# sirius1.net
KiCad netlist of a schematic drawn in EAGLE
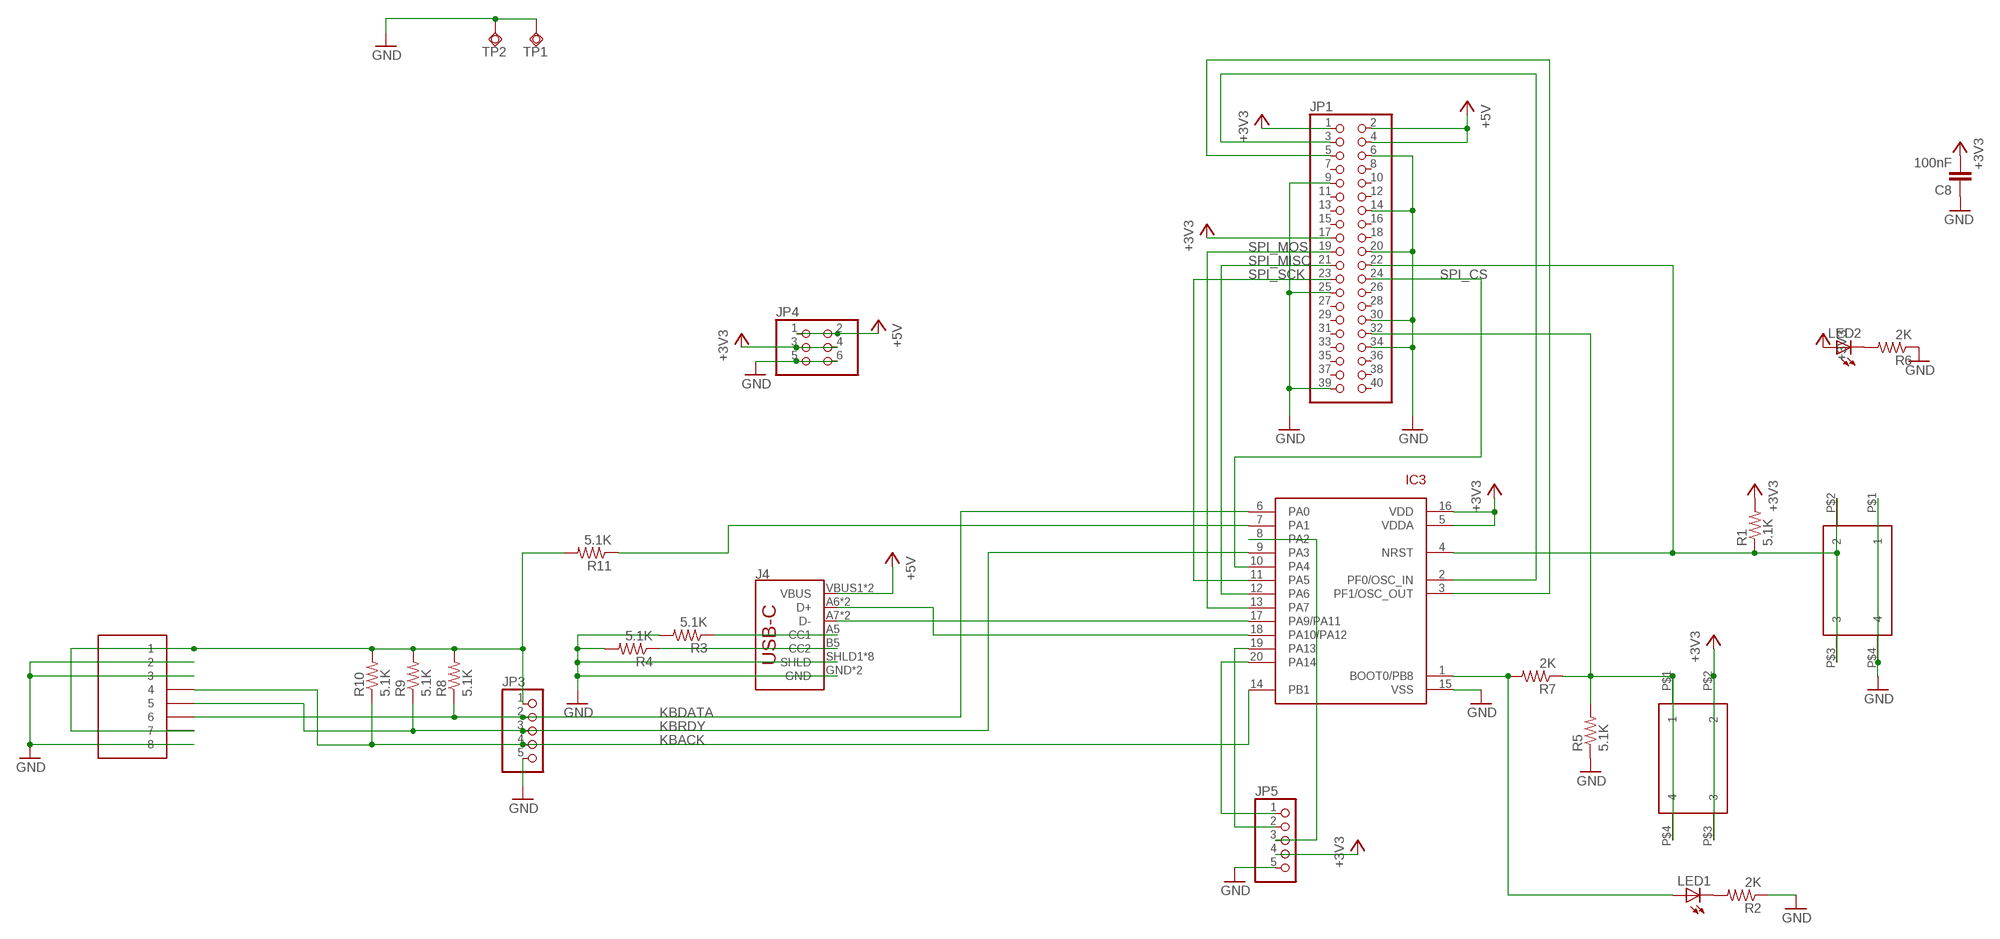
[diagram p0: schematic, sheet 1, part 1 of 2]
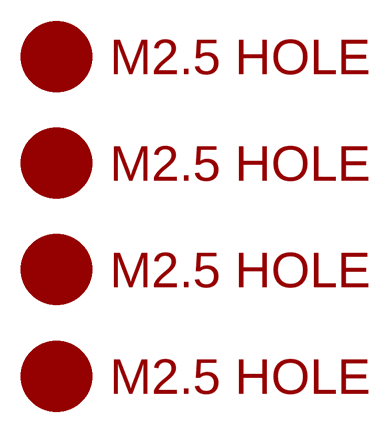
[diagram p1: schematic, sheet 1, part 2 of 2]

(export (version "E")
  (design (tool "Eeschema 10.0.6"))
  (components
    (comp (ref "C8")
      (value "100nF")
      (footprint "eagle-import:0805@1")
      (libsource (lib "eagle-import") (part "CAP0805"))
    )
    (comp (ref "IC3")
      (value "STM32F042F4")
      (footprint "eagle-import:TSSOP20")
      (libsource (lib "eagle-import") (part "STM32F042F4"))
    )
    (comp (ref "J4")
      (value "USB_C16PIN")
      (footprint "eagle-import:USB-C-16P")
      (libsource (lib "eagle-import") (part "USB_C16PIN"))
    )
    (comp (ref "JP1")
      (value "PINHD-2X20-BIG")
      (footprint "eagle-import:2X20-BIG")
      (libsource (lib "eagle-import") (part "PINHD-2X20-BIG"))
    )
    (comp (ref "JP3")
      (value "PINHD-1X5")
      (footprint "eagle-import:1X05")
      (libsource (lib "eagle-import") (part "PINHD-1X5"))
    )
    (comp (ref "JP4")
      (value "PINHD-2X3")
      (footprint "eagle-import:2X03")
      (libsource (lib "eagle-import") (part "PINHD-2X3"))
    )
    (comp (ref "JP5")
      (value "PINHD-1X5")
      (footprint "eagle-import:1X05")
      (libsource (lib "eagle-import") (part "PINHD-1X5"))
    )
    (comp (ref "LED1")
      (value "LEDCHIP-LED0805")
      (footprint "eagle-import:CHIP-LED0805")
      (libsource (lib "eagle-import") (part "LEDCHIP-LED0805"))
    )
    (comp (ref "LED2")
      (value "LEDCHIP-LED0805")
      (footprint "eagle-import:CHIP-LED0805")
      (libsource (lib "eagle-import") (part "LEDCHIP-LED0805"))
    )
    (comp (ref "R1")
      (value "5.1K")
      (footprint "eagle-import:0805")
      (libsource (lib "eagle-import") (part "RESISTOR0805-RES"))
    )
    (comp (ref "R2")
      (value "2K")
      (footprint "eagle-import:0805")
      (libsource (lib "eagle-import") (part "RESISTOR0805-RES"))
    )
    (comp (ref "R3")
      (value "5.1K")
      (footprint "eagle-import:0805")
      (libsource (lib "eagle-import") (part "RESISTOR0805-RES"))
    )
    (comp (ref "R4")
      (value "5.1K")
      (footprint "eagle-import:0805")
      (libsource (lib "eagle-import") (part "RESISTOR0805-RES"))
    )
    (comp (ref "R5")
      (value "5.1K")
      (footprint "eagle-import:0805")
      (libsource (lib "eagle-import") (part "RESISTOR0805-RES"))
    )
    (comp (ref "R6")
      (value "2K")
      (footprint "eagle-import:0805")
      (libsource (lib "eagle-import") (part "RESISTOR0805-RES"))
    )
    (comp (ref "R7")
      (value "2K")
      (footprint "eagle-import:0805")
      (libsource (lib "eagle-import") (part "RESISTOR0805-RES"))
    )
    (comp (ref "R8")
      (value "5.1K")
      (footprint "eagle-import:0805")
      (libsource (lib "eagle-import") (part "RESISTOR0805-RES"))
    )
    (comp (ref "R9")
      (value "5.1K")
      (footprint "eagle-import:0805")
      (libsource (lib "eagle-import") (part "RESISTOR0805-RES"))
    )
    (comp (ref "R10")
      (value "5.1K")
      (footprint "eagle-import:0805")
      (libsource (lib "eagle-import") (part "RESISTOR0805-RES"))
    )
    (comp (ref "R11")
      (value "5.1K")
      (footprint "eagle-import:0805")
      (libsource (lib "eagle-import") (part "RESISTOR0805-RES"))
    )
    (comp (ref "SW1")
      (value "324_SW")
      (footprint "eagle-import:342_SWICH_FOOT")
      (libsource (lib "eagle-import") (part "324_SW"))
    )
    (comp (ref "SW4")
      (value "324_SW")
      (footprint "eagle-import:342_SWICH_FOOT")
      (libsource (lib "eagle-import") (part "324_SW"))
    )
    (comp (ref "TP1")
      (value "TPSQPAD1-20")
      (footprint "eagle-import:P1-20")
      (libsource (lib "eagle-import") (part "TPSQPAD1-20"))
    )
    (comp (ref "TP2")
      (value "TPSQPAD1-20")
      (footprint "eagle-import:P1-20")
      (libsource (lib "eagle-import") (part "TPSQPAD1-20"))
    )
    (comp (ref "U$2")
      (value "M2.5HOLE")
      (footprint "eagle-import:M2.5HOLE")
      (libsource (lib "eagle-import") (part "M2.5HOLE"))
    )
    (comp (ref "U$3")
      (value "M2.5HOLE")
      (footprint "eagle-import:M2.5HOLE")
      (libsource (lib "eagle-import") (part "M2.5HOLE"))
    )
    (comp (ref "U$4")
      (value "M2.5HOLE")
      (footprint "eagle-import:M2.5HOLE")
      (libsource (lib "eagle-import") (part "M2.5HOLE"))
    )
    (comp (ref "U$5")
      (value "M2.5HOLE")
      (footprint "eagle-import:M2.5HOLE")
      (libsource (lib "eagle-import") (part "M2.5HOLE"))
    )
    (comp (ref "U1")
      (value "RJ45")
      (footprint "eagle-import:RJ45-8")
      (libsource (lib "eagle-import") (part "RJ45-8PTH"))
    )
  )
  (nets
    (net (code "1") (name "+3V3") (class "Default")
      (node (ref "C8") (pin "2") (pinfunction "2_2") (pintype "passive"))
      (node (ref "IC3") (pin "16") (pinfunction "VDD_16") (pintype "bidirectional"))
      (node (ref "IC3") (pin "5") (pinfunction "VDDA_5") (pintype "bidirectional"))
      (node (ref "JP1") (pin "1") (pinfunction "1_1") (pintype "passive"))
      (node (ref "JP1") (pin "17") (pinfunction "17_17") (pintype "passive"))
      (node (ref "JP4") (pin "3") (pinfunction "3_3") (pintype "passive"))
      (node (ref "JP4") (pin "4") (pinfunction "4_4") (pintype "passive"))
      (node (ref "JP5") (pin "4") (pinfunction "4_4") (pintype "passive"))
      (node (ref "LED2") (pin "A") (pinfunction "A_A") (pintype "passive"))
      (node (ref "R1") (pin "2") (pinfunction "2_2") (pintype "passive"))
      (node (ref "SW1") (pin "P$2") (pinfunction "2_P$2") (pintype "bidirectional"))
      (node (ref "SW1") (pin "P$3") (pinfunction "3_P$3") (pintype "bidirectional"))
    )
    (net (code "2") (name "+5V") (class "Default")
      (node (ref "J4") (pin "VBUS1") (pinfunction "VBUS_VBUS1") (pintype "bidirectional"))
      (node (ref "J4") (pin "VBUS2") (pinfunction "VBUS_VBUS2") (pintype "bidirectional"))
      (node (ref "JP1") (pin "2") (pinfunction "2_2") (pintype "passive"))
      (node (ref "JP1") (pin "4") (pinfunction "4_4") (pintype "passive"))
      (node (ref "JP4") (pin "1") (pinfunction "1_1") (pintype "passive"))
      (node (ref "JP4") (pin "2") (pinfunction "2_2") (pintype "passive"))
    )
    (net (code "3") (name "/KBACK") (class "Default")
      (node (ref "IC3") (pin "14") (pinfunction "PB1_14") (pintype "bidirectional"))
      (node (ref "JP3") (pin "4") (pinfunction "4_4") (pintype "passive"))
      (node (ref "R10") (pin "1") (pinfunction "1_1") (pintype "passive"))
      (node (ref "U1") (pin "4") (pinfunction "4_4") (pintype "bidirectional"))
    )
    (net (code "4") (name "/KBDATA") (class "Default")
      (node (ref "IC3") (pin "6") (pinfunction "PA0_6") (pintype "bidirectional"))
      (node (ref "JP3") (pin "2") (pinfunction "2_2") (pintype "passive"))
      (node (ref "R8") (pin "1") (pinfunction "1_1") (pintype "passive"))
      (node (ref "U1") (pin "6") (pinfunction "6_6") (pintype "bidirectional"))
    )
    (net (code "5") (name "/KBRDY") (class "Default")
      (node (ref "IC3") (pin "9") (pinfunction "PA3_9") (pintype "bidirectional"))
      (node (ref "JP3") (pin "3") (pinfunction "3_3") (pintype "passive"))
      (node (ref "R9") (pin "1") (pinfunction "1_1") (pintype "passive"))
      (node (ref "U1") (pin "5") (pinfunction "5_5") (pintype "bidirectional"))
    )
    (net (code "6") (name "/SPI_CS") (class "Default")
      (node (ref "IC3") (pin "10") (pinfunction "PA4_10") (pintype "bidirectional"))
      (node (ref "JP1") (pin "24") (pinfunction "24_24") (pintype "passive"))
    )
    (net (code "7") (name "/SPI_MISO") (class "Default")
      (node (ref "IC3") (pin "12") (pinfunction "PA6_12") (pintype "bidirectional"))
      (node (ref "JP1") (pin "21") (pinfunction "21_21") (pintype "passive"))
    )
    (net (code "8") (name "/SPI_MOSI") (class "Default")
      (node (ref "IC3") (pin "13") (pinfunction "PA7_13") (pintype "bidirectional"))
      (node (ref "JP1") (pin "19") (pinfunction "19_19") (pintype "passive"))
    )
    (net (code "9") (name "/SPI_SCK") (class "Default")
      (node (ref "IC3") (pin "11") (pinfunction "PA5_11") (pintype "bidirectional"))
      (node (ref "JP1") (pin "23") (pinfunction "23_23") (pintype "passive"))
    )
    (net (code "10") (name "GND") (class "Default")
      (node (ref "C8") (pin "1") (pinfunction "1_1") (pintype "passive"))
      (node (ref "IC3") (pin "15") (pinfunction "VSS_15") (pintype "bidirectional"))
      (node (ref "J4") (pin "GND") (pinfunction "GND_GND") (pintype "bidirectional"))
      (node (ref "J4") (pin "GND2") (pinfunction "GND_GND2") (pintype "bidirectional"))
      (node (ref "J4") (pin "SHLD1") (pinfunction "SHLD_SHLD1") (pintype "bidirectional"))
      (node (ref "J4") (pin "SHLD2") (pinfunction "SHLD_SHLD2") (pintype "bidirectional"))
      (node (ref "J4") (pin "SHLD3") (pinfunction "SHLD_SHLD3") (pintype "bidirectional"))
      (node (ref "J4") (pin "SHLD4") (pinfunction "SHLD_SHLD4") (pintype "bidirectional"))
      (node (ref "J4") (pin "SHLD5") (pinfunction "SHLD_SHLD5") (pintype "bidirectional"))
      (node (ref "J4") (pin "SHLD6") (pinfunction "SHLD_SHLD6") (pintype "bidirectional"))
      (node (ref "J4") (pin "SHLD7") (pinfunction "SHLD_SHLD7") (pintype "bidirectional"))
      (node (ref "J4") (pin "SHLD8") (pinfunction "SHLD_SHLD8") (pintype "bidirectional"))
      (node (ref "JP1") (pin "14") (pinfunction "14_14") (pintype "passive"))
      (node (ref "JP1") (pin "20") (pinfunction "20_20") (pintype "passive"))
      (node (ref "JP1") (pin "25") (pinfunction "25_25") (pintype "passive"))
      (node (ref "JP1") (pin "30") (pinfunction "30_30") (pintype "passive"))
      (node (ref "JP1") (pin "34") (pinfunction "34_34") (pintype "passive"))
      (node (ref "JP1") (pin "39") (pinfunction "39_39") (pintype "passive"))
      (node (ref "JP1") (pin "6") (pinfunction "6_6") (pintype "passive"))
      (node (ref "JP1") (pin "9") (pinfunction "9_9") (pintype "passive"))
      (node (ref "JP3") (pin "5") (pinfunction "5_5") (pintype "passive"))
      (node (ref "JP4") (pin "5") (pinfunction "5_5") (pintype "passive"))
      (node (ref "JP4") (pin "6") (pinfunction "6_6") (pintype "passive"))
      (node (ref "JP5") (pin "5") (pinfunction "5_5") (pintype "passive"))
      (node (ref "R2") (pin "1") (pinfunction "1_1") (pintype "passive"))
      (node (ref "R3") (pin "2") (pinfunction "2_2") (pintype "passive"))
      (node (ref "R4") (pin "2") (pinfunction "2_2") (pintype "passive"))
      (node (ref "R5") (pin "1") (pinfunction "1_1") (pintype "passive"))
      (node (ref "R6") (pin "1") (pinfunction "1_1") (pintype "passive"))
      (node (ref "SW4") (pin "P$1") (pinfunction "1_P$1") (pintype "bidirectional"))
      (node (ref "SW4") (pin "P$4") (pinfunction "4_P$4") (pintype "bidirectional"))
      (node (ref "TP1") (pin "TP") (pinfunction "TP_TP") (pintype "input"))
      (node (ref "TP2") (pin "TP") (pinfunction "TP_TP") (pintype "input"))
      (node (ref "U1") (pin "2") (pinfunction "2_2") (pintype "bidirectional"))
      (node (ref "U1") (pin "3") (pinfunction "3_3") (pintype "bidirectional"))
      (node (ref "U1") (pin "8") (pinfunction "8_8") (pintype "bidirectional"))
    )
    (net (code "11") (name "Net-(IC3-BOOT0{slash}PB8)") (class "Default")
      (node (ref "IC3") (pin "1") (pinfunction "BOOT0/PB8_1") (pintype "bidirectional"))
      (node (ref "LED1") (pin "A") (pinfunction "A_A") (pintype "passive"))
      (node (ref "R7") (pin "2") (pinfunction "2_2") (pintype "passive"))
    )
    (net (code "12") (name "Net-(IC3-NRST)") (class "Default")
      (node (ref "IC3") (pin "4") (pinfunction "NRST_4") (pintype "bidirectional"))
      (node (ref "JP1") (pin "22") (pinfunction "22_22") (pintype "passive"))
      (node (ref "R1") (pin "1") (pinfunction "1_1") (pintype "passive"))
      (node (ref "SW4") (pin "P$2") (pinfunction "2_P$2") (pintype "bidirectional"))
      (node (ref "SW4") (pin "P$3") (pinfunction "3_P$3") (pintype "bidirectional"))
    )
    (net (code "13") (name "Net-(IC3-PA1)") (class "Default")
      (node (ref "IC3") (pin "7") (pinfunction "PA1_7") (pintype "bidirectional"))
      (node (ref "R11") (pin "1") (pinfunction "1_1") (pintype "passive"))
    )
    (net (code "14") (name "Net-(IC3-PA2)") (class "Default")
      (node (ref "IC3") (pin "8") (pinfunction "PA2_8") (pintype "bidirectional"))
      (node (ref "JP5") (pin "3") (pinfunction "3_3") (pintype "passive"))
    )
    (net (code "15") (name "Net-(IC3-PA9{slash}PA11)") (class "Default")
      (node (ref "IC3") (pin "17") (pinfunction "PA9/PA11_17") (pintype "bidirectional"))
      (node (ref "J4") (pin "A7") (pinfunction "D-_A7") (pintype "bidirectional"))
      (node (ref "J4") (pin "B7") (pinfunction "D-_B7") (pintype "bidirectional"))
    )
    (net (code "16") (name "Net-(IC3-PA10{slash}PA12)") (class "Default")
      (node (ref "IC3") (pin "18") (pinfunction "PA10/PA12_18") (pintype "bidirectional"))
      (node (ref "J4") (pin "A6") (pinfunction "D+_A6") (pintype "bidirectional"))
      (node (ref "J4") (pin "B6") (pinfunction "D+_B6") (pintype "bidirectional"))
    )
    (net (code "17") (name "Net-(IC3-PA13)") (class "Default")
      (node (ref "IC3") (pin "19") (pinfunction "PA13_19") (pintype "bidirectional"))
      (node (ref "JP5") (pin "2") (pinfunction "2_2") (pintype "passive"))
    )
    (net (code "18") (name "Net-(IC3-PA14)") (class "Default")
      (node (ref "IC3") (pin "20") (pinfunction "PA14_20") (pintype "bidirectional"))
      (node (ref "JP5") (pin "1") (pinfunction "1_1") (pintype "passive"))
    )
    (net (code "19") (name "Net-(IC3-PF0{slash}OSC_IN)") (class "Default")
      (node (ref "IC3") (pin "2") (pinfunction "PF0/OSC_IN_2") (pintype "bidirectional"))
      (node (ref "JP1") (pin "3") (pinfunction "3_3") (pintype "passive"))
    )
    (net (code "20") (name "Net-(IC3-PF1{slash}OSC_OUT)") (class "Default")
      (node (ref "IC3") (pin "3") (pinfunction "PF1/OSC_OUT_3") (pintype "bidirectional"))
      (node (ref "JP1") (pin "5") (pinfunction "5_5") (pintype "passive"))
    )
    (net (code "21") (name "Net-(J4-CC1)") (class "Default")
      (node (ref "J4") (pin "A5") (pinfunction "CC1_A5") (pintype "bidirectional"))
      (node (ref "R3") (pin "1") (pinfunction "1_1") (pintype "passive"))
    )
    (net (code "22") (name "Net-(J4-CC2)") (class "Default")
      (node (ref "J4") (pin "B5") (pinfunction "CC2_B5") (pintype "bidirectional"))
      (node (ref "R4") (pin "1") (pinfunction "1_1") (pintype "passive"))
    )
    (net (code "23") (name "Net-(JP3-Pad1)") (class "Default")
      (node (ref "JP3") (pin "1") (pinfunction "1_1") (pintype "passive"))
      (node (ref "R10") (pin "2") (pinfunction "2_2") (pintype "passive"))
      (node (ref "R11") (pin "2") (pinfunction "2_2") (pintype "passive"))
      (node (ref "R8") (pin "2") (pinfunction "2_2") (pintype "passive"))
      (node (ref "R9") (pin "2") (pinfunction "2_2") (pintype "passive"))
      (node (ref "U1") (pin "1") (pinfunction "1_1") (pintype "bidirectional"))
      (node (ref "U1") (pin "7") (pinfunction "7_7") (pintype "bidirectional"))
    )
    (net (code "24") (name "Net-(LED1-PadC)") (class "Default")
      (node (ref "LED1") (pin "C") (pinfunction "C_C") (pintype "passive"))
      (node (ref "R2") (pin "2") (pinfunction "2_2") (pintype "passive"))
    )
    (net (code "25") (name "Net-(LED2-PadC)") (class "Default")
      (node (ref "LED2") (pin "C") (pinfunction "C_C") (pintype "passive"))
      (node (ref "R6") (pin "2") (pinfunction "2_2") (pintype "passive"))
    )
    (net (code "26") (name "Net-(SW1-1)") (class "Default")
      (node (ref "JP1") (pin "32") (pinfunction "32_32") (pintype "passive"))
      (node (ref "R5") (pin "2") (pinfunction "2_2") (pintype "passive"))
      (node (ref "R7") (pin "1") (pinfunction "1_1") (pintype "passive"))
      (node (ref "SW1") (pin "P$1") (pinfunction "1_P$1") (pintype "bidirectional"))
      (node (ref "SW1") (pin "P$4") (pinfunction "4_P$4") (pintype "bidirectional"))
    )
    (net (code "27") (name "unconnected-(JP1-Pad7)") (class "Default")
      (node (ref "JP1") (pin "7") (pinfunction "7_7") (pintype "passive"))
    )
    (net (code "28") (name "unconnected-(JP1-Pad8)") (class "Default")
      (node (ref "JP1") (pin "8") (pinfunction "8_8") (pintype "passive"))
    )
    (net (code "29") (name "unconnected-(JP1-Pad10)") (class "Default")
      (node (ref "JP1") (pin "10") (pinfunction "10_10") (pintype "passive"))
    )
    (net (code "30") (name "unconnected-(JP1-Pad11)") (class "Default")
      (node (ref "JP1") (pin "11") (pinfunction "11_11") (pintype "passive"))
    )
    (net (code "31") (name "unconnected-(JP1-Pad12)") (class "Default")
      (node (ref "JP1") (pin "12") (pinfunction "12_12") (pintype "passive"))
    )
    (net (code "32") (name "unconnected-(JP1-Pad13)") (class "Default")
      (node (ref "JP1") (pin "13") (pinfunction "13_13") (pintype "passive"))
    )
    (net (code "33") (name "unconnected-(JP1-Pad15)") (class "Default")
      (node (ref "JP1") (pin "15") (pinfunction "15_15") (pintype "passive"))
    )
    (net (code "34") (name "unconnected-(JP1-Pad16)") (class "Default")
      (node (ref "JP1") (pin "16") (pinfunction "16_16") (pintype "passive"))
    )
    (net (code "35") (name "unconnected-(JP1-Pad18)") (class "Default")
      (node (ref "JP1") (pin "18") (pinfunction "18_18") (pintype "passive"))
    )
    (net (code "36") (name "unconnected-(JP1-Pad26)") (class "Default")
      (node (ref "JP1") (pin "26") (pinfunction "26_26") (pintype "passive"))
    )
    (net (code "37") (name "unconnected-(JP1-Pad27)") (class "Default")
      (node (ref "JP1") (pin "27") (pinfunction "27_27") (pintype "passive"))
    )
    (net (code "38") (name "unconnected-(JP1-Pad28)") (class "Default")
      (node (ref "JP1") (pin "28") (pinfunction "28_28") (pintype "passive"))
    )
    (net (code "39") (name "unconnected-(JP1-Pad29)") (class "Default")
      (node (ref "JP1") (pin "29") (pinfunction "29_29") (pintype "passive"))
    )
    (net (code "40") (name "unconnected-(JP1-Pad31)") (class "Default")
      (node (ref "JP1") (pin "31") (pinfunction "31_31") (pintype "passive"))
    )
    (net (code "41") (name "unconnected-(JP1-Pad33)") (class "Default")
      (node (ref "JP1") (pin "33") (pinfunction "33_33") (pintype "passive"))
    )
    (net (code "42") (name "unconnected-(JP1-Pad35)") (class "Default")
      (node (ref "JP1") (pin "35") (pinfunction "35_35") (pintype "passive"))
    )
    (net (code "43") (name "unconnected-(JP1-Pad36)") (class "Default")
      (node (ref "JP1") (pin "36") (pinfunction "36_36") (pintype "passive"))
    )
    (net (code "44") (name "unconnected-(JP1-Pad37)") (class "Default")
      (node (ref "JP1") (pin "37") (pinfunction "37_37") (pintype "passive"))
    )
    (net (code "45") (name "unconnected-(JP1-Pad38)") (class "Default")
      (node (ref "JP1") (pin "38") (pinfunction "38_38") (pintype "passive"))
    )
    (net (code "46") (name "unconnected-(JP1-Pad40)") (class "Default")
      (node (ref "JP1") (pin "40") (pinfunction "40_40") (pintype "passive"))
    )
  )
)
